# tinycopter_v2.net
KiCad netlist of a schematic drawn in EAGLE
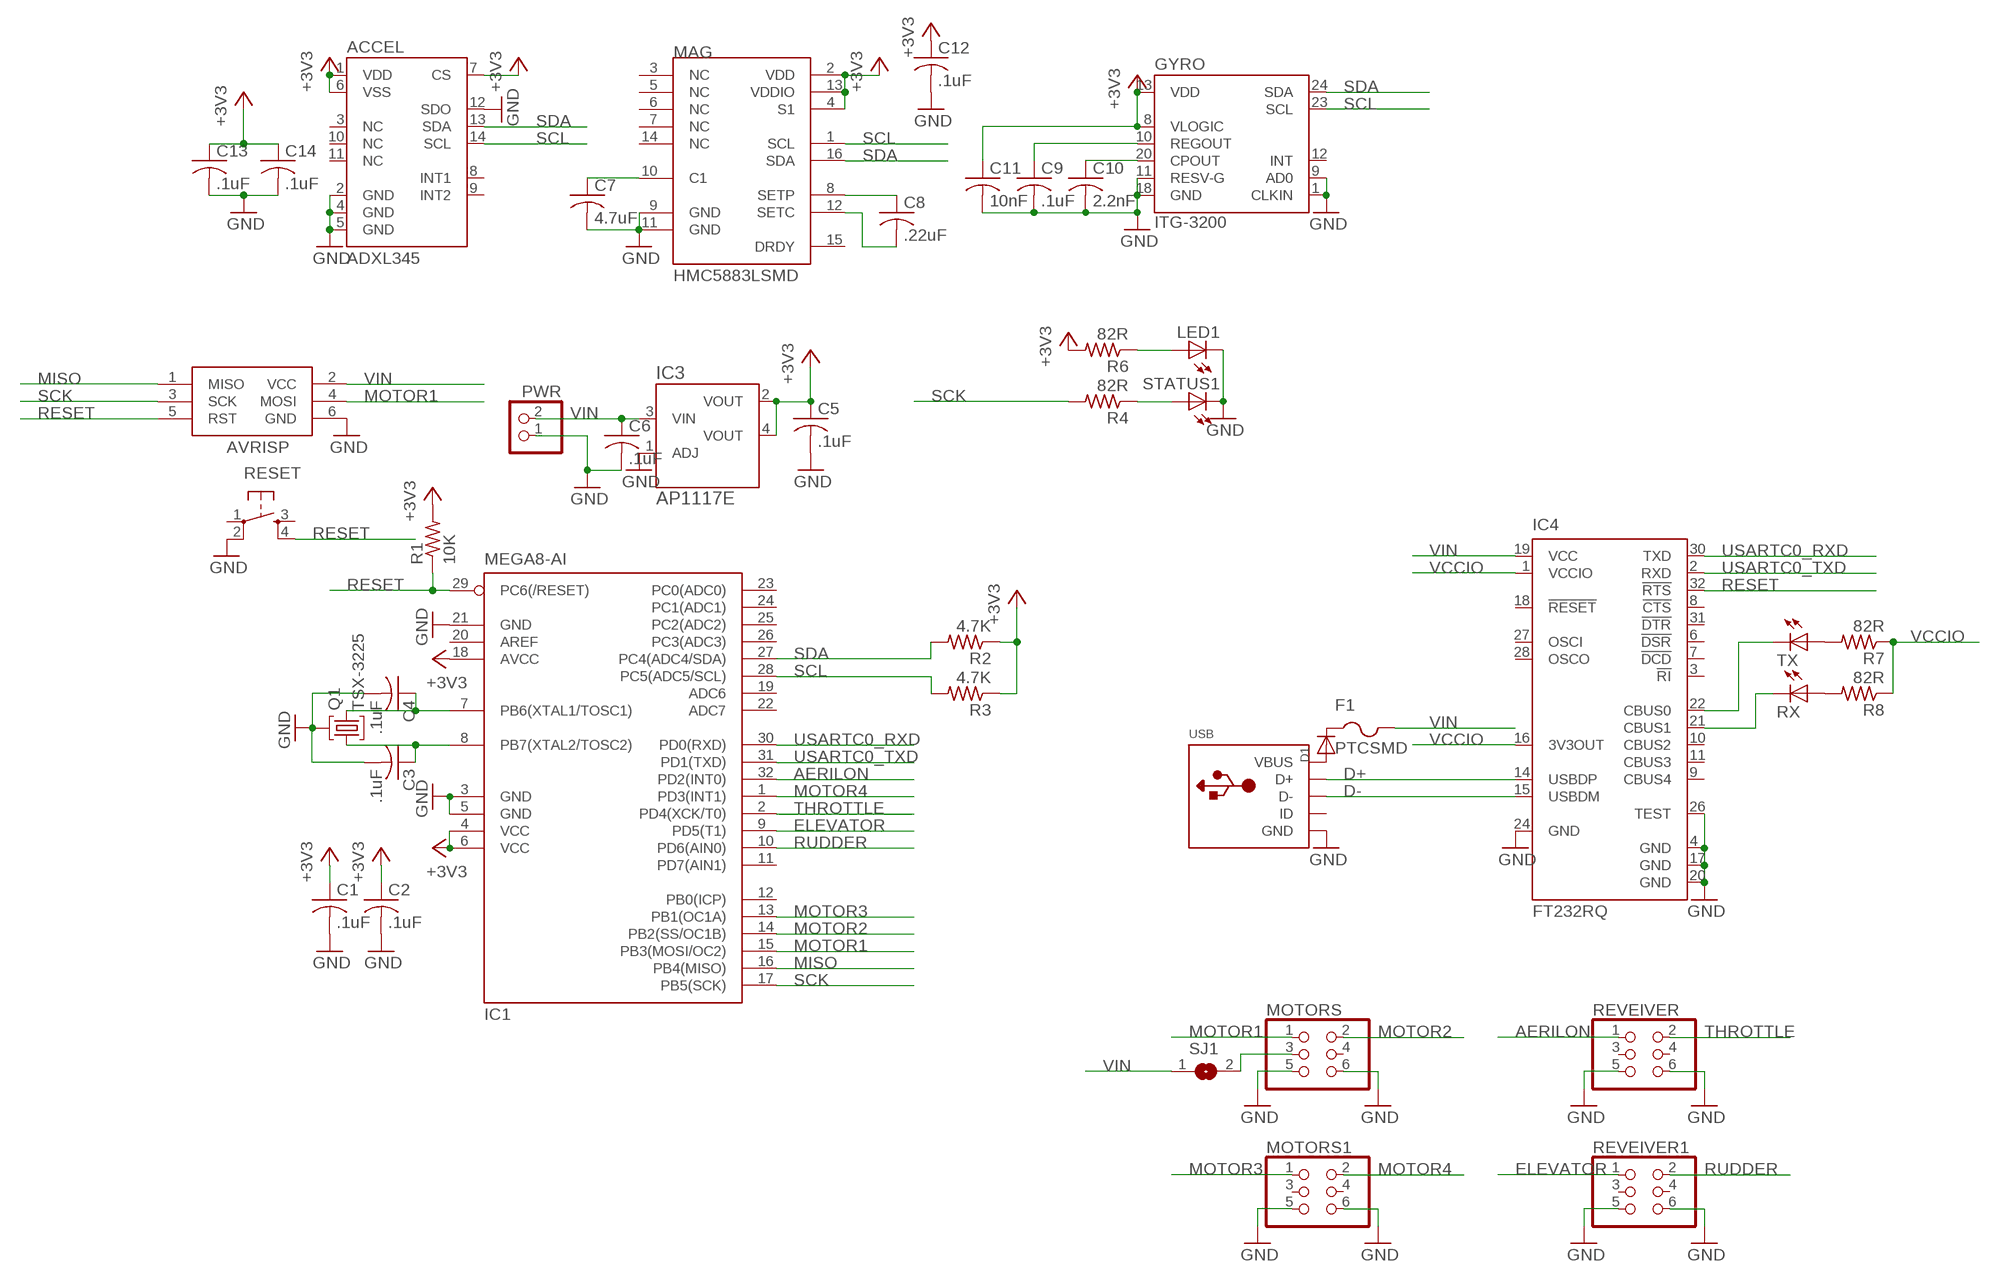
[diagram p0: schematic, sheet 1]

(export (version "E")
  (design (tool "Eeschema 10.0.6"))
  (components
    (comp (ref "ACCEL")
      (value "ADXL345")
      (footprint "eagle-import:LGA14")
      (libsource (lib "eagle-import") (part "ADXL345"))
    )
    (comp (ref "AVRISP")
      (value "AVRISP-6")
      (footprint "eagle-import:AVRISP")
      (libsource (lib "eagle-import") (part "AVRISP-6"))
    )
    (comp (ref "C1")
      (value ".1uF")
      (footprint "eagle-import:C0603")
      (libsource (lib "eagle-import") (part "C-USC0603"))
    )
    (comp (ref "C2")
      (value ".1uF")
      (footprint "eagle-import:C0603")
      (libsource (lib "eagle-import") (part "C-USC0603"))
    )
    (comp (ref "C3")
      (value ".1uF")
      (footprint "eagle-import:C0603")
      (libsource (lib "eagle-import") (part "C-USC0603"))
    )
    (comp (ref "C4")
      (value ".1uF")
      (footprint "eagle-import:C0603")
      (libsource (lib "eagle-import") (part "C-USC0603"))
    )
    (comp (ref "C5")
      (value ".1uF")
      (footprint "eagle-import:C0603")
      (libsource (lib "eagle-import") (part "C-USC0603"))
    )
    (comp (ref "C6")
      (value ".1uF")
      (footprint "eagle-import:C0603")
      (libsource (lib "eagle-import") (part "C-USC0603"))
    )
    (comp (ref "C7")
      (value "4.7uF")
      (footprint "eagle-import:C0805K")
      (libsource (lib "eagle-import") (part "C-USC0805K"))
    )
    (comp (ref "C8")
      (value ".22uF")
      (footprint "eagle-import:C0603")
      (libsource (lib "eagle-import") (part "C-USC0603"))
    )
    (comp (ref "C9")
      (value ".1uF")
      (footprint "eagle-import:C0603")
      (libsource (lib "eagle-import") (part "C-USC0603"))
    )
    (comp (ref "C10")
      (value "2.2nF")
      (footprint "eagle-import:C0603")
      (libsource (lib "eagle-import") (part "C-USC0603"))
    )
    (comp (ref "C11")
      (value "10nF")
      (footprint "eagle-import:C0603")
      (libsource (lib "eagle-import") (part "C-USC0603"))
    )
    (comp (ref "C12")
      (value ".1uF")
      (footprint "eagle-import:C0603")
      (libsource (lib "eagle-import") (part "C-USC0603"))
    )
    (comp (ref "C13")
      (value ".1uF")
      (footprint "eagle-import:C0603")
      (libsource (lib "eagle-import") (part "C-USC0603"))
    )
    (comp (ref "C14")
      (value ".1uF")
      (footprint "eagle-import:C0603")
      (libsource (lib "eagle-import") (part "C-USC0603"))
    )
    (comp (ref "D1")
      (value "DIODESOD-123")
      (footprint "eagle-import:SOD-123")
      (libsource (lib "eagle-import") (part "DIODESOD-123"))
    )
    (comp (ref "F1")
      (value "PTCSMD")
      (footprint "eagle-import:1812")
      (libsource (lib "eagle-import") (part "PTCFUSE-1812"))
    )
    (comp (ref "GYRO")
      (value "ITG-3200")
      (footprint "eagle-import:QFN-24")
      (libsource (lib "eagle-import") (part "ITG-3200"))
    )
    (comp (ref "IC1")
      (value "MEGA8-AI")
      (footprint "eagle-import:TQFP32-08")
      (fields (field (name "MPN") "ATMEGA8-16AU"))
      (libsource (lib "eagle-import") (part "MEGA8-AI"))
    )
    (comp (ref "IC3")
      (value "AP1117E")
      (footprint "eagle-import:SOT223-3")
      (libsource (lib "eagle-import") (part "AP1117E"))
    )
    (comp (ref "IC4")
      (value "FT232RQ")
      (footprint "eagle-import:QFN32")
      (libsource (lib "eagle-import") (part "FT232RQ"))
    )
    (comp (ref "LED1")
      (value "LEDCHIP-LED0805")
      (footprint "eagle-import:CHIP-LED0805")
      (libsource (lib "eagle-import") (part "LEDCHIP-LED0805"))
    )
    (comp (ref "MAG")
      (value "HMC5883LSMD")
      (footprint "eagle-import:16LPCC")
      (libsource (lib "eagle-import") (part "HMC5883LSMD"))
    )
    (comp (ref "MOTORS")
      (value "PINHD-2X3")
      (footprint "eagle-import:2X03")
      (libsource (lib "eagle-import") (part "PINHD-2X3"))
    )
    (comp (ref "MOTORS1")
      (value "PINHD-2X3")
      (footprint "eagle-import:2X03")
      (libsource (lib "eagle-import") (part "PINHD-2X3"))
    )
    (comp (ref "PWR")
      (value "JST_2PIN-THM")
      (footprint "eagle-import:JST-PH-2-THM")
      (libsource (lib "eagle-import") (part "JST_2PIN-THM"))
    )
    (comp (ref "Q1")
      (value "TSX-3225")
      (footprint "eagle-import:TSX-3225")
      (libsource (lib "eagle-import") (part "TSX-3225"))
    )
    (comp (ref "R1")
      (value "10K")
      (footprint "eagle-import:R0603")
      (libsource (lib "eagle-import") (part "R-US_R0603"))
    )
    (comp (ref "R2")
      (value "4.7K")
      (footprint "eagle-import:R0603")
      (libsource (lib "eagle-import") (part "R-US_R0603"))
    )
    (comp (ref "R3")
      (value "4.7K")
      (footprint "eagle-import:R0603")
      (libsource (lib "eagle-import") (part "R-US_R0603"))
    )
    (comp (ref "R4")
      (value "82R")
      (footprint "eagle-import:R0603")
      (libsource (lib "eagle-import") (part "R-US_R0603"))
    )
    (comp (ref "R6")
      (value "82R")
      (footprint "eagle-import:R0603")
      (libsource (lib "eagle-import") (part "R-US_R0603"))
    )
    (comp (ref "R7")
      (value "82R")
      (footprint "eagle-import:R0603")
      (libsource (lib "eagle-import") (part "R-US_R0603"))
    )
    (comp (ref "R8")
      (value "82R")
      (footprint "eagle-import:R0603")
      (libsource (lib "eagle-import") (part "R-US_R0603"))
    )
    (comp (ref "RESET")
      (value "TAC_SWITCHSMD")
      (footprint "eagle-import:TACTILE_SWITCH_SMD")
      (libsource (lib "eagle-import") (part "TAC_SWITCHSMD"))
    )
    (comp (ref "REVEIVER")
      (value "PINHD-2X3")
      (footprint "eagle-import:2X03")
      (libsource (lib "eagle-import") (part "PINHD-2X3"))
    )
    (comp (ref "REVEIVER1")
      (value "PINHD-2X3")
      (footprint "eagle-import:2X03")
      (libsource (lib "eagle-import") (part "PINHD-2X3"))
    )
    (comp (ref "RX")
      (value "LEDCHIP-LED0805")
      (footprint "eagle-import:CHIP-LED0805")
      (libsource (lib "eagle-import") (part "LEDCHIP-LED0805"))
    )
    (comp (ref "SJ1") (value "SJ") (footprint "eagle-import:SJ") (libsource (lib "eagle-import") (part "SJ")))
    (comp (ref "STATUS1")
      (value "LEDCHIP-LED0805")
      (footprint "eagle-import:CHIP-LED0805")
      (libsource (lib "eagle-import") (part "LEDCHIP-LED0805"))
    )
    (comp (ref "TX")
      (value "LEDCHIP-LED0805")
      (footprint "eagle-import:CHIP-LED0805")
      (libsource (lib "eagle-import") (part "LEDCHIP-LED0805"))
    )
    (comp (ref "USB")
      (value "USBMINIB")
      (footprint "eagle-import:USB-MINIB")
      (libsource (lib "eagle-import") (part "USBMINIB"))
    )
  )
  (nets
    (net (code "1") (name "+3V3") (class "Default")
      (node (ref "ACCEL") (pin "1") (pinfunction "VDD_1") (pintype "bidirectional"))
      (node (ref "ACCEL") (pin "6") (pinfunction "VSS_6") (pintype "bidirectional"))
      (node (ref "ACCEL") (pin "7") (pinfunction "CS_7") (pintype "bidirectional"))
      (node (ref "C1") (pin "1") (pinfunction "1_1") (pintype "passive"))
      (node (ref "C11") (pin "1") (pinfunction "1_1") (pintype "passive"))
      (node (ref "C12") (pin "1") (pinfunction "1_1") (pintype "passive"))
      (node (ref "C13") (pin "1") (pinfunction "1_1") (pintype "passive"))
      (node (ref "C14") (pin "1") (pinfunction "1_1") (pintype "passive"))
      (node (ref "C2") (pin "1") (pinfunction "1_1") (pintype "passive"))
      (node (ref "C5") (pin "1") (pinfunction "1_1") (pintype "passive"))
      (node (ref "GYRO") (pin "13") (pinfunction "VDD_13") (pintype "bidirectional"))
      (node (ref "GYRO") (pin "8") (pinfunction "VLOGIC_8") (pintype "bidirectional"))
      (node (ref "IC1") (pin "18") (pinfunction "AVCC_18") (pintype "power_in"))
      (node (ref "IC1") (pin "4") (pinfunction "VCC_4") (pintype "power_in"))
      (node (ref "IC1") (pin "6") (pinfunction "VCC_6") (pintype "power_in"))
      (node (ref "IC3") (pin "2") (pinfunction "VOUT_2") (pintype "bidirectional"))
      (node (ref "IC3") (pin "4") (pinfunction "VOUT_4") (pintype "bidirectional"))
      (node (ref "MAG") (pin "13") (pinfunction "VDDIO_13") (pintype "bidirectional"))
      (node (ref "MAG") (pin "2") (pinfunction "VDD_2") (pintype "bidirectional"))
      (node (ref "MAG") (pin "4") (pinfunction "S1_4") (pintype "bidirectional"))
      (node (ref "R1") (pin "2") (pinfunction "2_2") (pintype "passive"))
      (node (ref "R2") (pin "1") (pinfunction "1_1") (pintype "passive"))
      (node (ref "R3") (pin "1") (pinfunction "1_1") (pintype "passive"))
      (node (ref "R6") (pin "2") (pinfunction "2_2") (pintype "passive"))
    )
    (net (code "2") (name "/AERILON") (class "Default")
      (node (ref "IC1") (pin "32") (pinfunction "PD2(INT0)_32") (pintype "bidirectional"))
      (node (ref "REVEIVER") (pin "1") (pinfunction "1_1") (pintype "passive"))
    )
    (net (code "3") (name "/D+") (class "Default")
      (node (ref "IC4") (pin "14") (pinfunction "USBDP_14") (pintype "bidirectional"))
      (node (ref "USB") (pin "D+") (pinfunction "D+_D+") (pintype "bidirectional"))
    )
    (net (code "4") (name "/D-") (class "Default")
      (node (ref "IC4") (pin "15") (pinfunction "USBDM_15") (pintype "bidirectional"))
      (node (ref "USB") (pin "D-") (pinfunction "D-_D-") (pintype "bidirectional"))
    )
    (net (code "5") (name "/ELEVATOR") (class "Default")
      (node (ref "IC1") (pin "9") (pinfunction "PD5(T1)_9") (pintype "bidirectional"))
      (node (ref "REVEIVER1") (pin "1") (pinfunction "1_1") (pintype "passive"))
    )
    (net (code "6") (name "/MISO") (class "Default")
      (node (ref "AVRISP") (pin "1") (pinfunction "MISO_1") (pintype "input"))
      (node (ref "IC1") (pin "16") (pinfunction "PB4(MISO)_16") (pintype "bidirectional"))
    )
    (net (code "7") (name "/MOTOR1") (class "Default")
      (node (ref "AVRISP") (pin "4") (pinfunction "MOSI_4") (pintype "output"))
      (node (ref "IC1") (pin "15") (pinfunction "PB3(MOSI/OC2)_15") (pintype "bidirectional"))
      (node (ref "MOTORS") (pin "1") (pinfunction "1_1") (pintype "passive"))
    )
    (net (code "8") (name "/MOTOR2") (class "Default")
      (node (ref "IC1") (pin "14") (pinfunction "PB2(SS/OC1B)_14") (pintype "bidirectional"))
      (node (ref "MOTORS") (pin "2") (pinfunction "2_2") (pintype "passive"))
    )
    (net (code "9") (name "/MOTOR3") (class "Default")
      (node (ref "IC1") (pin "13") (pinfunction "PB1(OC1A)_13") (pintype "bidirectional"))
      (node (ref "MOTORS1") (pin "1") (pinfunction "1_1") (pintype "passive"))
    )
    (net (code "10") (name "/MOTOR4") (class "Default")
      (node (ref "IC1") (pin "1") (pinfunction "PD3(INT1)_1") (pintype "bidirectional"))
      (node (ref "MOTORS1") (pin "2") (pinfunction "2_2") (pintype "passive"))
    )
    (net (code "11") (name "/RESET") (class "Default")
      (node (ref "AVRISP") (pin "5") (pinfunction "RST_5") (pintype "output"))
      (node (ref "IC1") (pin "29") (pinfunction "PC6(/RESET)_29") (pintype "bidirectional"))
      (node (ref "IC4") (pin "32") (pinfunction "~{RTS}_32") (pintype "output"))
      (node (ref "R1") (pin "1") (pinfunction "1_1") (pintype "passive"))
      (node (ref "RESET") (pin "4") (pinfunction "4_4") (pintype "passive"))
    )
    (net (code "12") (name "/RUDDER") (class "Default")
      (node (ref "IC1") (pin "10") (pinfunction "PD6(AIN0)_10") (pintype "bidirectional"))
      (node (ref "REVEIVER1") (pin "2") (pinfunction "2_2") (pintype "passive"))
    )
    (net (code "13") (name "/SCK") (class "Default")
      (node (ref "AVRISP") (pin "3") (pinfunction "SCK_3") (pintype "output"))
      (node (ref "IC1") (pin "17") (pinfunction "PB5(SCK)_17") (pintype "bidirectional"))
      (node (ref "R4") (pin "2") (pinfunction "2_2") (pintype "passive"))
    )
    (net (code "14") (name "/SCL") (class "Default")
      (node (ref "ACCEL") (pin "14") (pinfunction "SCL_14") (pintype "bidirectional"))
      (node (ref "GYRO") (pin "23") (pinfunction "SCL_23") (pintype "bidirectional"))
      (node (ref "IC1") (pin "28") (pinfunction "PC5(ADC5/SCL)_28") (pintype "bidirectional"))
      (node (ref "MAG") (pin "1") (pinfunction "SCL_1") (pintype "bidirectional"))
      (node (ref "R3") (pin "2") (pinfunction "2_2") (pintype "passive"))
    )
    (net (code "15") (name "/SDA") (class "Default")
      (node (ref "ACCEL") (pin "13") (pinfunction "SDA_13") (pintype "bidirectional"))
      (node (ref "GYRO") (pin "24") (pinfunction "SDA_24") (pintype "bidirectional"))
      (node (ref "IC1") (pin "27") (pinfunction "PC4(ADC4/SDA)_27") (pintype "bidirectional"))
      (node (ref "MAG") (pin "16") (pinfunction "SDA_16") (pintype "bidirectional"))
      (node (ref "R2") (pin "2") (pinfunction "2_2") (pintype "passive"))
    )
    (net (code "16") (name "/THROTTLE") (class "Default")
      (node (ref "IC1") (pin "2") (pinfunction "PD4(XCK/T0)_2") (pintype "bidirectional"))
      (node (ref "REVEIVER") (pin "2") (pinfunction "2_2") (pintype "passive"))
    )
    (net (code "17") (name "/USARTC0_RXD") (class "Default")
      (node (ref "IC1") (pin "30") (pinfunction "PD0(RXD)_30") (pintype "bidirectional"))
      (node (ref "IC4") (pin "30") (pinfunction "TXD_30") (pintype "output"))
    )
    (net (code "18") (name "/USARTC0_TXD") (class "Default")
      (node (ref "IC1") (pin "31") (pinfunction "PD1(TXD)_31") (pintype "bidirectional"))
      (node (ref "IC4") (pin "2") (pinfunction "RXD_2") (pintype "input"))
    )
    (net (code "19") (name "/VCCIO") (class "Default")
      (node (ref "IC4") (pin "1") (pinfunction "VCCIO_1") (pintype "power_in"))
      (node (ref "IC4") (pin "16") (pinfunction "3V3OUT_16") (pintype "output"))
      (node (ref "R7") (pin "1") (pinfunction "1_1") (pintype "passive"))
      (node (ref "R8") (pin "1") (pinfunction "1_1") (pintype "passive"))
    )
    (net (code "20") (name "/VIN") (class "Default")
      (node (ref "AVRISP") (pin "2") (pinfunction "VCC_2") (pintype "power_in"))
      (node (ref "C6") (pin "1") (pinfunction "1_1") (pintype "passive"))
      (node (ref "F1") (pin "2") (pinfunction "2_2") (pintype "passive"))
      (node (ref "IC3") (pin "3") (pinfunction "VIN_3") (pintype "bidirectional"))
      (node (ref "IC4") (pin "19") (pinfunction "VCC_19") (pintype "power_in"))
      (node (ref "PWR") (pin "2") (pinfunction "1_2") (pintype "passive"))
      (node (ref "SJ1") (pin "1") (pinfunction "1_1") (pintype "passive"))
    )
    (net (code "21") (name "GND") (class "Default")
      (node (ref "ACCEL") (pin "12") (pinfunction "SDO_12") (pintype "bidirectional"))
      (node (ref "ACCEL") (pin "2") (pinfunction "GND_2") (pintype "bidirectional"))
      (node (ref "ACCEL") (pin "4") (pinfunction "GND_4") (pintype "bidirectional"))
      (node (ref "ACCEL") (pin "5") (pinfunction "GND_5") (pintype "bidirectional"))
      (node (ref "AVRISP") (pin "6") (pinfunction "GND_6") (pintype "power_in"))
      (node (ref "C1") (pin "2") (pinfunction "2_2") (pintype "passive"))
      (node (ref "C10") (pin "2") (pinfunction "2_2") (pintype "passive"))
      (node (ref "C11") (pin "2") (pinfunction "2_2") (pintype "passive"))
      (node (ref "C12") (pin "2") (pinfunction "2_2") (pintype "passive"))
      (node (ref "C13") (pin "2") (pinfunction "2_2") (pintype "passive"))
      (node (ref "C14") (pin "2") (pinfunction "2_2") (pintype "passive"))
      (node (ref "C2") (pin "2") (pinfunction "2_2") (pintype "passive"))
      (node (ref "C3") (pin "2") (pinfunction "2_2") (pintype "passive"))
      (node (ref "C4") (pin "2") (pinfunction "2_2") (pintype "passive"))
      (node (ref "C5") (pin "2") (pinfunction "2_2") (pintype "passive"))
      (node (ref "C6") (pin "2") (pinfunction "2_2") (pintype "passive"))
      (node (ref "C7") (pin "2") (pinfunction "2_2") (pintype "passive"))
      (node (ref "C9") (pin "2") (pinfunction "2_2") (pintype "passive"))
      (node (ref "GYRO") (pin "1") (pinfunction "CLKIN_1") (pintype "bidirectional"))
      (node (ref "GYRO") (pin "11") (pinfunction "RESV-G_11") (pintype "bidirectional"))
      (node (ref "GYRO") (pin "18") (pinfunction "GND_18") (pintype "bidirectional"))
      (node (ref "GYRO") (pin "9") (pinfunction "AD0_9") (pintype "bidirectional"))
      (node (ref "IC1") (pin "21") (pinfunction "GND_21") (pintype "power_in"))
      (node (ref "IC1") (pin "3") (pinfunction "GND_3") (pintype "power_in"))
      (node (ref "IC1") (pin "5") (pinfunction "GND_5") (pintype "power_in"))
      (node (ref "IC3") (pin "1") (pinfunction "ADJ_1") (pintype "bidirectional"))
      (node (ref "IC4") (pin "17") (pinfunction "GND_17") (pintype "power_in"))
      (node (ref "IC4") (pin "20") (pinfunction "GND_20") (pintype "power_in"))
      (node (ref "IC4") (pin "24") (pinfunction "GND_24") (pintype "power_in"))
      (node (ref "IC4") (pin "26") (pinfunction "TEST_26") (pintype "input"))
      (node (ref "IC4") (pin "4") (pinfunction "GND_4") (pintype "power_in"))
      (node (ref "LED1") (pin "C") (pinfunction "C_C") (pintype "passive"))
      (node (ref "MAG") (pin "11") (pinfunction "GND_11") (pintype "bidirectional"))
      (node (ref "MAG") (pin "9") (pinfunction "GND_9") (pintype "bidirectional"))
      (node (ref "MOTORS") (pin "5") (pinfunction "5_5") (pintype "passive"))
      (node (ref "MOTORS") (pin "6") (pinfunction "6_6") (pintype "passive"))
      (node (ref "MOTORS1") (pin "5") (pinfunction "5_5") (pintype "passive"))
      (node (ref "MOTORS1") (pin "6") (pinfunction "6_6") (pintype "passive"))
      (node (ref "PWR") (pin "1") (pinfunction "2_1") (pintype "passive"))
      (node (ref "Q1") (pin "2") (pinfunction "3_2") (pintype "passive"))
      (node (ref "Q1") (pin "4") (pinfunction "3_4") (pintype "passive"))
      (node (ref "RESET") (pin "2") (pinfunction "2_2") (pintype "passive"))
      (node (ref "REVEIVER") (pin "5") (pinfunction "5_5") (pintype "passive"))
      (node (ref "REVEIVER") (pin "6") (pinfunction "6_6") (pintype "passive"))
      (node (ref "REVEIVER1") (pin "5") (pinfunction "5_5") (pintype "passive"))
      (node (ref "REVEIVER1") (pin "6") (pinfunction "6_6") (pintype "passive"))
      (node (ref "STATUS1") (pin "C") (pinfunction "C_C") (pintype "passive"))
      (node (ref "USB") (pin "GND") (pinfunction "GND_GND") (pintype "power_in"))
    )
    (net (code "22") (name "Net-(D1-PadA)") (class "Default")
      (node (ref "D1") (pin "A") (pinfunction "A_A") (pintype "passive"))
      (node (ref "USB") (pin "VBUS") (pinfunction "VBUS_VBUS") (pintype "power_in"))
    )
    (net (code "23") (name "Net-(D1-PadC)") (class "Default")
      (node (ref "D1") (pin "C") (pinfunction "C_C") (pintype "passive"))
      (node (ref "F1") (pin "1") (pinfunction "1_1") (pintype "passive"))
    )
    (net (code "24") (name "Net-(GYRO-CPOUT)") (class "Default")
      (node (ref "C10") (pin "1") (pinfunction "1_1") (pintype "passive"))
      (node (ref "GYRO") (pin "20") (pinfunction "CPOUT_20") (pintype "bidirectional"))
    )
    (net (code "25") (name "Net-(GYRO-REGOUT)") (class "Default")
      (node (ref "C9") (pin "1") (pinfunction "1_1") (pintype "passive"))
      (node (ref "GYRO") (pin "10") (pinfunction "REGOUT_10") (pintype "bidirectional"))
    )
    (net (code "26") (name "Net-(IC1-PB6(XTAL1{slash}TOSC1))") (class "Default")
      (node (ref "C4") (pin "1") (pinfunction "1_1") (pintype "passive"))
      (node (ref "IC1") (pin "7") (pinfunction "PB6(XTAL1/TOSC1)_7") (pintype "bidirectional"))
      (node (ref "Q1") (pin "3") (pinfunction "2_3") (pintype "passive"))
    )
    (net (code "27") (name "Net-(IC1-PB7(XTAL2{slash}TOSC2))") (class "Default")
      (node (ref "C3") (pin "1") (pinfunction "1_1") (pintype "passive"))
      (node (ref "IC1") (pin "8") (pinfunction "PB7(XTAL2/TOSC2)_8") (pintype "bidirectional"))
      (node (ref "Q1") (pin "1") (pinfunction "1_1") (pintype "passive"))
    )
    (net (code "28") (name "Net-(IC4-CBUS0)") (class "Default")
      (node (ref "IC4") (pin "22") (pinfunction "CBUS0_22") (pintype "bidirectional"))
      (node (ref "TX") (pin "C") (pinfunction "C_C") (pintype "passive"))
    )
    (net (code "29") (name "Net-(IC4-CBUS1)") (class "Default")
      (node (ref "IC4") (pin "21") (pinfunction "CBUS1_21") (pintype "bidirectional"))
      (node (ref "RX") (pin "C") (pinfunction "C_C") (pintype "passive"))
    )
    (net (code "30") (name "Net-(LED1-PadA)") (class "Default")
      (node (ref "LED1") (pin "A") (pinfunction "A_A") (pintype "passive"))
      (node (ref "R6") (pin "1") (pinfunction "1_1") (pintype "passive"))
    )
    (net (code "31") (name "Net-(MAG-C1)") (class "Default")
      (node (ref "C7") (pin "1") (pinfunction "1_1") (pintype "passive"))
      (node (ref "MAG") (pin "10") (pinfunction "C1_10") (pintype "bidirectional"))
    )
    (net (code "32") (name "Net-(MAG-SETC)") (class "Default")
      (node (ref "C8") (pin "2") (pinfunction "2_2") (pintype "passive"))
      (node (ref "MAG") (pin "12") (pinfunction "SETC_12") (pintype "bidirectional"))
    )
    (net (code "33") (name "Net-(MAG-SETP)") (class "Default")
      (node (ref "C8") (pin "1") (pinfunction "1_1") (pintype "passive"))
      (node (ref "MAG") (pin "8") (pinfunction "SETP_8") (pintype "bidirectional"))
    )
    (net (code "34") (name "Net-(MOTORS-Pad3)") (class "Default")
      (node (ref "MOTORS") (pin "3") (pinfunction "3_3") (pintype "passive"))
      (node (ref "SJ1") (pin "2") (pinfunction "2_2") (pintype "passive"))
    )
    (net (code "35") (name "Net-(R4-Pad1)") (class "Default")
      (node (ref "R4") (pin "1") (pinfunction "1_1") (pintype "passive"))
      (node (ref "STATUS1") (pin "A") (pinfunction "A_A") (pintype "passive"))
    )
    (net (code "36") (name "Net-(R7-Pad2)") (class "Default")
      (node (ref "R7") (pin "2") (pinfunction "2_2") (pintype "passive"))
      (node (ref "TX") (pin "A") (pinfunction "A_A") (pintype "passive"))
    )
    (net (code "37") (name "Net-(R8-Pad2)") (class "Default")
      (node (ref "R8") (pin "2") (pinfunction "2_2") (pintype "passive"))
      (node (ref "RX") (pin "A") (pinfunction "A_A") (pintype "passive"))
    )
    (net (code "38") (name "unconnected-(ACCEL-INT1-Pad8)") (class "Default")
      (node (ref "ACCEL") (pin "8") (pinfunction "INT1_8") (pintype "bidirectional"))
    )
    (net (code "39") (name "unconnected-(ACCEL-INT2-Pad9)") (class "Default")
      (node (ref "ACCEL") (pin "9") (pinfunction "INT2_9") (pintype "bidirectional"))
    )
    (net (code "40") (name "unconnected-(ACCEL-NC-Pad3)") (class "Default")
      (node (ref "ACCEL") (pin "3") (pinfunction "NC_3") (pintype "bidirectional"))
    )
    (net (code "41") (name "unconnected-(ACCEL-NC-Pad10)") (class "Default")
      (node (ref "ACCEL") (pin "10") (pinfunction "NC_10") (pintype "bidirectional"))
    )
    (net (code "42") (name "unconnected-(ACCEL-NC-Pad11)") (class "Default")
      (node (ref "ACCEL") (pin "11") (pinfunction "NC_11") (pintype "bidirectional"))
    )
    (net (code "43") (name "unconnected-(GYRO-INT-Pad12)") (class "Default")
      (node (ref "GYRO") (pin "12") (pinfunction "INT_12") (pintype "bidirectional"))
    )
    (net (code "44") (name "unconnected-(IC1-ADC6-Pad19)") (class "Default")
      (node (ref "IC1") (pin "19") (pinfunction "ADC6_19") (pintype "bidirectional"))
    )
    (net (code "45") (name "unconnected-(IC1-ADC7-Pad22)") (class "Default")
      (node (ref "IC1") (pin "22") (pinfunction "ADC7_22") (pintype "bidirectional"))
    )
    (net (code "46") (name "unconnected-(IC1-AREF-Pad20)") (class "Default")
      (node (ref "IC1") (pin "20") (pinfunction "AREF_20") (pintype "passive"))
    )
    (net (code "47") (name "unconnected-(IC1-PB0(ICP)-Pad12)") (class "Default")
      (node (ref "IC1") (pin "12") (pinfunction "PB0(ICP)_12") (pintype "bidirectional"))
    )
    (net (code "48") (name "unconnected-(IC1-PC0(ADC0)-Pad23)") (class "Default")
      (node (ref "IC1") (pin "23") (pinfunction "PC0(ADC0)_23") (pintype "bidirectional"))
    )
    (net (code "49") (name "unconnected-(IC1-PC1(ADC1)-Pad24)") (class "Default")
      (node (ref "IC1") (pin "24") (pinfunction "PC1(ADC1)_24") (pintype "bidirectional"))
    )
    (net (code "50") (name "unconnected-(IC1-PC2(ADC2)-Pad25)") (class "Default")
      (node (ref "IC1") (pin "25") (pinfunction "PC2(ADC2)_25") (pintype "bidirectional"))
    )
    (net (code "51") (name "unconnected-(IC1-PC3(ADC3)-Pad26)") (class "Default")
      (node (ref "IC1") (pin "26") (pinfunction "PC3(ADC3)_26") (pintype "bidirectional"))
    )
    (net (code "52") (name "unconnected-(IC1-PD7(AIN1)-Pad11)") (class "Default")
      (node (ref "IC1") (pin "11") (pinfunction "PD7(AIN1)_11") (pintype "bidirectional"))
    )
    (net (code "53") (name "unconnected-(IC4-CBUS2-Pad10)") (class "Default")
      (node (ref "IC4") (pin "10") (pinfunction "CBUS2_10") (pintype "bidirectional"))
    )
    (net (code "54") (name "unconnected-(IC4-CBUS3-Pad11)") (class "Default")
      (node (ref "IC4") (pin "11") (pinfunction "CBUS3_11") (pintype "bidirectional"))
    )
    (net (code "55") (name "unconnected-(IC4-CBUS4-Pad9)") (class "Default")
      (node (ref "IC4") (pin "9") (pinfunction "CBUS4_9") (pintype "bidirectional"))
    )
    (net (code "56") (name "unconnected-(IC4-OSCI-Pad27)") (class "Default")
      (node (ref "IC4") (pin "27") (pinfunction "OSCI_27") (pintype "input"))
    )
    (net (code "57") (name "unconnected-(IC4-OSCO-Pad28)") (class "Default")
      (node (ref "IC4") (pin "28") (pinfunction "OSCO_28") (pintype "output"))
    )
    (net (code "58") (name "unconnected-(IC4-~{CTS}-Pad8)") (class "Default")
      (node (ref "IC4") (pin "8") (pinfunction "~{CTS}_8") (pintype "input"))
    )
    (net (code "59") (name "unconnected-(IC4-~{DCD}-Pad7)") (class "Default")
      (node (ref "IC4") (pin "7") (pinfunction "~{DCD}_7") (pintype "input"))
    )
    (net (code "60") (name "unconnected-(IC4-~{DSR}-Pad6)") (class "Default")
      (node (ref "IC4") (pin "6") (pinfunction "~{DSR}_6") (pintype "input"))
    )
    (net (code "61") (name "unconnected-(IC4-~{DTR}-Pad31)") (class "Default")
      (node (ref "IC4") (pin "31") (pinfunction "~{DTR}_31") (pintype "output"))
    )
    (net (code "62") (name "unconnected-(IC4-~{RESET}-Pad18)") (class "Default")
      (node (ref "IC4") (pin "18") (pinfunction "~{RESET}_18") (pintype "input"))
    )
    (net (code "63") (name "unconnected-(IC4-~{RI}-Pad3)") (class "Default")
      (node (ref "IC4") (pin "3") (pinfunction "~{RI}_3") (pintype "input"))
    )
    (net (code "64") (name "unconnected-(MAG-DRDY-Pad15)") (class "Default")
      (node (ref "MAG") (pin "15") (pinfunction "DRDY_15") (pintype "bidirectional"))
    )
    (net (code "65") (name "unconnected-(MAG-NC-Pad3)") (class "Default")
      (node (ref "MAG") (pin "3") (pinfunction "NC_3") (pintype "bidirectional"))
    )
    (net (code "66") (name "unconnected-(MAG-NC-Pad5)") (class "Default")
      (node (ref "MAG") (pin "5") (pinfunction "NC_5") (pintype "bidirectional"))
    )
    (net (code "67") (name "unconnected-(MAG-NC-Pad6)") (class "Default")
      (node (ref "MAG") (pin "6") (pinfunction "NC_6") (pintype "bidirectional"))
    )
    (net (code "68") (name "unconnected-(MAG-NC-Pad7)") (class "Default")
      (node (ref "MAG") (pin "7") (pinfunction "NC_7") (pintype "bidirectional"))
    )
    (net (code "69") (name "unconnected-(MAG-NC-Pad14)") (class "Default")
      (node (ref "MAG") (pin "14") (pinfunction "NC_14") (pintype "bidirectional"))
    )
    (net (code "70") (name "unconnected-(MOTORS-Pad4)") (class "Default")
      (node (ref "MOTORS") (pin "4") (pinfunction "4_4") (pintype "passive"))
    )
    (net (code "71") (name "unconnected-(MOTORS1-Pad3)") (class "Default")
      (node (ref "MOTORS1") (pin "3") (pinfunction "3_3") (pintype "passive"))
    )
    (net (code "72") (name "unconnected-(MOTORS1-Pad4)") (class "Default")
      (node (ref "MOTORS1") (pin "4") (pinfunction "4_4") (pintype "passive"))
    )
    (net (code "73") (name "unconnected-(RESET-Pad1)") (class "Default")
      (node (ref "RESET") (pin "1") (pinfunction "1_1") (pintype "passive"))
    )
    (net (code "74") (name "unconnected-(RESET-Pad3)") (class "Default")
      (node (ref "RESET") (pin "3") (pinfunction "3_3") (pintype "passive"))
    )
    (net (code "75") (name "unconnected-(REVEIVER-Pad3)") (class "Default")
      (node (ref "REVEIVER") (pin "3") (pinfunction "3_3") (pintype "passive"))
    )
    (net (code "76") (name "unconnected-(REVEIVER-Pad4)") (class "Default")
      (node (ref "REVEIVER") (pin "4") (pinfunction "4_4") (pintype "passive"))
    )
    (net (code "77") (name "unconnected-(REVEIVER1-Pad3)") (class "Default")
      (node (ref "REVEIVER1") (pin "3") (pinfunction "3_3") (pintype "passive"))
    )
    (net (code "78") (name "unconnected-(REVEIVER1-Pad4)") (class "Default")
      (node (ref "REVEIVER1") (pin "4") (pinfunction "4_4") (pintype "passive"))
    )
    (net (code "79") (name "unconnected-(USB-PadID)") (class "Default")
      (node (ref "USB") (pin "ID") (pinfunction "ID_ID") (pintype "bidirectional"))
    )
  )
)
